# GateDrive_schem.net
KiCad netlist of a schematic drawn in Altium Designer
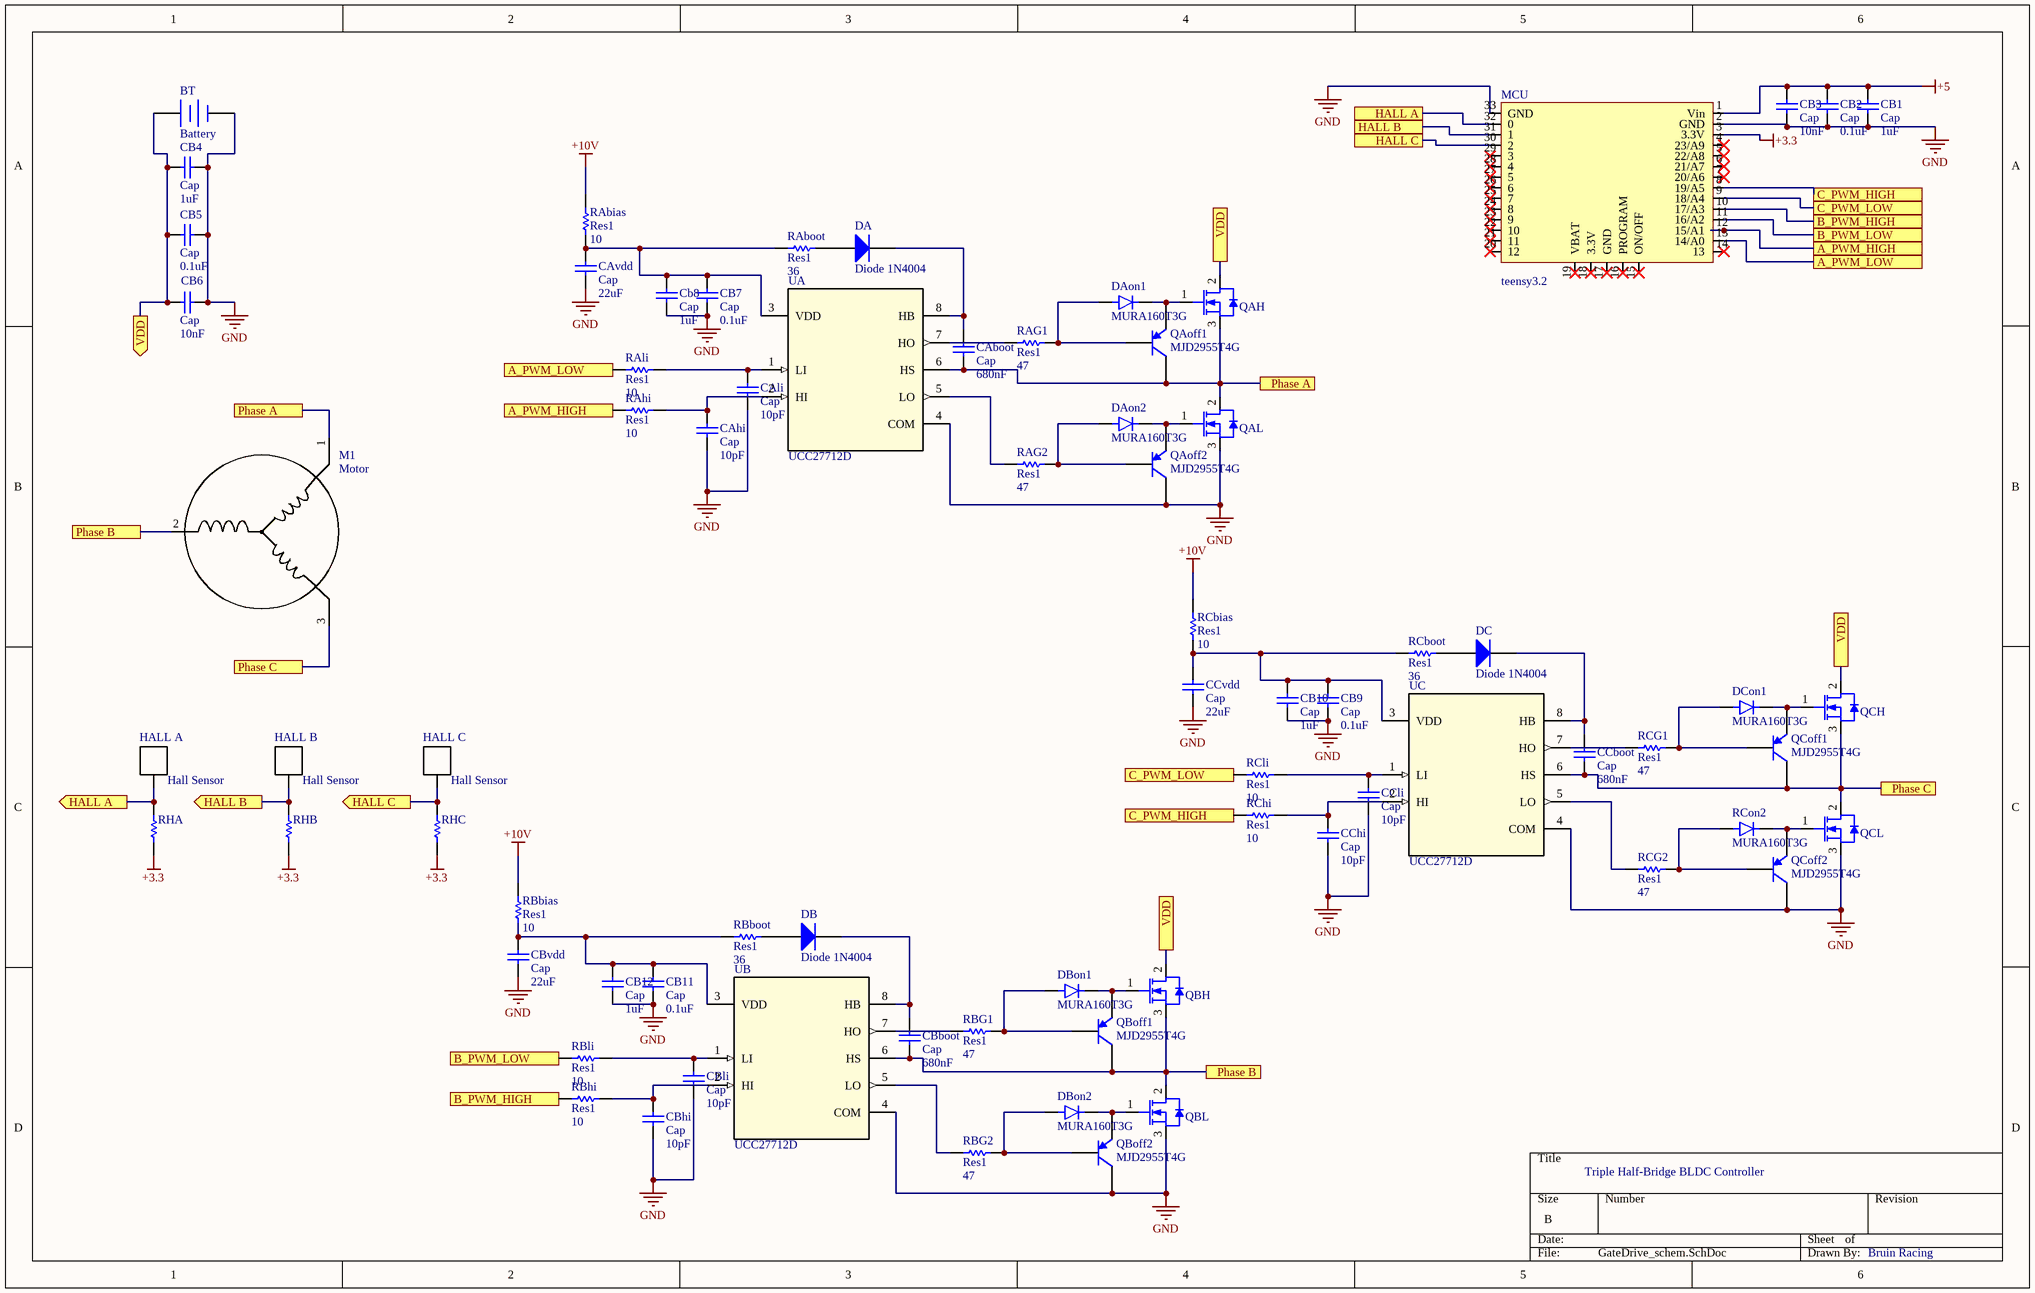
[diagram p0: GateDrive_schem.SchDoc]

(export (version "E")
  (design (tool "Eeschema 10.0.6"))
  (components
    (comp (ref "BT")
      (value "Battery")
      (footprint "BAT-2")
      (description "Multicell Battery")
      (fields (field (name "PUBLISHER") "Altium Limited"))
      (libsource (lib "Miscellaneous Devices") (part "Battery"))
    )
    (comp (ref "CAboot")
      (value "Cap")
      (footprint "RAD-0.3")
      (description "Capacitor")
      (fields (field (name "ALTIUM_VALUE") "680nF") (field (name "PUBLISHER") "Altium Limited"))
      (libsource (lib "Miscellaneous Devices") (part "Cap"))
    )
    (comp (ref "CAhi")
      (value "Cap")
      (footprint "RAD-0.3")
      (description "Capacitor")
      (fields (field (name "ALTIUM_VALUE") "10pF") (field (name "PUBLISHER") "Altium Limited"))
      (libsource (lib "Miscellaneous Devices") (part "Cap"))
    )
    (comp (ref "CAli")
      (value "Cap")
      (footprint "RAD-0.3")
      (description "Capacitor")
      (fields (field (name "ALTIUM_VALUE") "10pF") (field (name "PUBLISHER") "Altium Limited"))
      (libsource (lib "Miscellaneous Devices") (part "Cap"))
    )
    (comp (ref "CAvdd")
      (value "Cap")
      (footprint "RAD-0.3")
      (description "Capacitor")
      (fields (field (name "ALTIUM_VALUE") "22uF") (field (name "PUBLISHER") "Altium Limited"))
      (libsource (lib "Miscellaneous Devices") (part "Cap"))
    )
    (comp (ref "CB1")
      (value "Cap")
      (footprint "RAD-0.3")
      (description "Capacitor")
      (fields (field (name "ALTIUM_VALUE") "1uF") (field (name "PUBLISHER") "Altium Limited"))
      (libsource (lib "Miscellaneous Devices") (part "Cap"))
    )
    (comp (ref "CB2")
      (value "Cap")
      (footprint "RAD-0.3")
      (description "Capacitor")
      (fields (field (name "ALTIUM_VALUE") "0.1uF") (field (name "PUBLISHER") "Altium Limited"))
      (libsource (lib "Miscellaneous Devices") (part "Cap"))
    )
    (comp (ref "CB3")
      (value "Cap")
      (footprint "RAD-0.3")
      (description "Capacitor")
      (fields (field (name "ALTIUM_VALUE") "10nF") (field (name "PUBLISHER") "Altium Limited"))
      (libsource (lib "Miscellaneous Devices") (part "Cap"))
    )
    (comp (ref "CB4")
      (value "Cap")
      (footprint "RAD-0.3")
      (description "Capacitor")
      (fields (field (name "ALTIUM_VALUE") "1uF") (field (name "PUBLISHER") "Altium Limited"))
      (libsource (lib "Miscellaneous Devices") (part "Cap"))
    )
    (comp (ref "CB5")
      (value "Cap")
      (footprint "RAD-0.3")
      (description "Capacitor")
      (fields (field (name "ALTIUM_VALUE") "0.1uF") (field (name "PUBLISHER") "Altium Limited"))
      (libsource (lib "Miscellaneous Devices") (part "Cap"))
    )
    (comp (ref "CB6")
      (value "Cap")
      (footprint "RAD-0.3")
      (description "Capacitor")
      (fields (field (name "ALTIUM_VALUE") "10nF") (field (name "PUBLISHER") "Altium Limited"))
      (libsource (lib "Miscellaneous Devices") (part "Cap"))
    )
    (comp (ref "CB7")
      (value "Cap")
      (footprint "RAD-0.3")
      (description "Capacitor")
      (fields (field (name "ALTIUM_VALUE") "0.1uF") (field (name "PUBLISHER") "Altium Limited"))
      (libsource (lib "Miscellaneous Devices") (part "Cap"))
    )
    (comp (ref "Cb8")
      (value "Cap")
      (footprint "RAD-0.3")
      (description "Capacitor")
      (fields (field (name "ALTIUM_VALUE") "1uF") (field (name "PUBLISHER") "Altium Limited"))
      (libsource (lib "Miscellaneous Devices") (part "Cap"))
    )
    (comp (ref "CB9")
      (value "Cap")
      (footprint "RAD-0.3")
      (description "Capacitor")
      (fields (field (name "ALTIUM_VALUE") "0.1uF") (field (name "PUBLISHER") "Altium Limited"))
      (libsource (lib "Miscellaneous Devices") (part "Cap"))
    )
    (comp (ref "CB10")
      (value "Cap")
      (footprint "RAD-0.3")
      (description "Capacitor")
      (fields (field (name "ALTIUM_VALUE") "1uF") (field (name "PUBLISHER") "Altium Limited"))
      (libsource (lib "Miscellaneous Devices") (part "Cap"))
    )
    (comp (ref "CB11")
      (value "Cap")
      (footprint "RAD-0.3")
      (description "Capacitor")
      (fields (field (name "ALTIUM_VALUE") "0.1uF") (field (name "PUBLISHER") "Altium Limited"))
      (libsource (lib "Miscellaneous Devices") (part "Cap"))
    )
    (comp (ref "CB12")
      (value "Cap")
      (footprint "RAD-0.3")
      (description "Capacitor")
      (fields (field (name "ALTIUM_VALUE") "1uF") (field (name "PUBLISHER") "Altium Limited"))
      (libsource (lib "Miscellaneous Devices") (part "Cap"))
    )
    (comp (ref "CBboot")
      (value "Cap")
      (footprint "RAD-0.3")
      (description "Capacitor")
      (fields (field (name "ALTIUM_VALUE") "680nF") (field (name "PUBLISHER") "Altium Limited"))
      (libsource (lib "Miscellaneous Devices") (part "Cap"))
    )
    (comp (ref "CBhi")
      (value "Cap")
      (footprint "RAD-0.3")
      (description "Capacitor")
      (fields (field (name "ALTIUM_VALUE") "10pF") (field (name "PUBLISHER") "Altium Limited"))
      (libsource (lib "Miscellaneous Devices") (part "Cap"))
    )
    (comp (ref "CBli")
      (value "Cap")
      (footprint "RAD-0.3")
      (description "Capacitor")
      (fields (field (name "ALTIUM_VALUE") "10pF") (field (name "PUBLISHER") "Altium Limited"))
      (libsource (lib "Miscellaneous Devices") (part "Cap"))
    )
    (comp (ref "CBvdd")
      (value "Cap")
      (footprint "RAD-0.3")
      (description "Capacitor")
      (fields (field (name "ALTIUM_VALUE") "22uF") (field (name "PUBLISHER") "Altium Limited"))
      (libsource (lib "Miscellaneous Devices") (part "Cap"))
    )
    (comp (ref "CCboot")
      (value "Cap")
      (footprint "RAD-0.3")
      (description "Capacitor")
      (fields (field (name "ALTIUM_VALUE") "680nF") (field (name "PUBLISHER") "Altium Limited"))
      (libsource (lib "Miscellaneous Devices") (part "Cap"))
    )
    (comp (ref "CChi")
      (value "Cap")
      (footprint "RAD-0.3")
      (description "Capacitor")
      (fields (field (name "ALTIUM_VALUE") "10pF") (field (name "PUBLISHER") "Altium Limited"))
      (libsource (lib "Miscellaneous Devices") (part "Cap"))
    )
    (comp (ref "CCli")
      (value "Cap")
      (footprint "RAD-0.3")
      (description "Capacitor")
      (fields (field (name "ALTIUM_VALUE") "10pF") (field (name "PUBLISHER") "Altium Limited"))
      (libsource (lib "Miscellaneous Devices") (part "Cap"))
    )
    (comp (ref "CCvdd")
      (value "Cap")
      (footprint "RAD-0.3")
      (description "Capacitor")
      (fields (field (name "ALTIUM_VALUE") "22uF") (field (name "PUBLISHER") "Altium Limited"))
      (libsource (lib "Miscellaneous Devices") (part "Cap"))
    )
    (comp (ref "DA")
      (value "Diode 1N4004")
      (footprint "DO-41")
      (description "1 Amp General Purpose Rectifier")
      (fields (field (name "PUBLISHER") "Altium Limited"))
      (libsource (lib "Miscellaneous Devices") (part "Diode 1N4004"))
    )
    (comp (ref "DAon1")
      (value "MURA160T3G")
      (footprint "DIOM5226X220N")
      (description "Diode Standard 600V 1A Surface Mount SMA")
      (fields (field (name "MF") "ON Semiconductor"))
      (libsource (lib "MURA160T3G") (part "MURA160T3G"))
    )
    (comp (ref "DAon2")
      (value "MURA160T3G")
      (footprint "DIOM5226X220N")
      (description "Diode Standard 600V 1A Surface Mount SMA")
      (fields (field (name "MF") "ON Semiconductor"))
      (libsource (lib "MURA160T3G") (part "MURA160T3G"))
    )
    (comp (ref "DB")
      (value "Diode 1N4004")
      (footprint "DO-41")
      (description "1 Amp General Purpose Rectifier")
      (fields (field (name "PUBLISHER") "Altium Limited"))
      (libsource (lib "Miscellaneous Devices") (part "Diode 1N4004"))
    )
    (comp (ref "DBon1")
      (value "MURA160T3G")
      (footprint "DIOM5226X220N")
      (description "Diode Standard 600V 1A Surface Mount SMA")
      (fields (field (name "MF") "ON Semiconductor"))
      (libsource (lib "MURA160T3G") (part "MURA160T3G"))
    )
    (comp (ref "DBon2")
      (value "MURA160T3G")
      (footprint "DIOM5226X220N")
      (description "Diode Standard 600V 1A Surface Mount SMA")
      (fields (field (name "MF") "ON Semiconductor"))
      (libsource (lib "MURA160T3G") (part "MURA160T3G"))
    )
    (comp (ref "DC")
      (value "Diode 1N4004")
      (footprint "DO-41")
      (description "1 Amp General Purpose Rectifier")
      (fields (field (name "PUBLISHER") "Altium Limited"))
      (libsource (lib "Miscellaneous Devices") (part "Diode 1N4004"))
    )
    (comp (ref "DCon1")
      (value "MURA160T3G")
      (footprint "DIOM5226X220N")
      (description "Diode Standard 600V 1A Surface Mount SMA")
      (fields (field (name "MF") "ON Semiconductor"))
      (libsource (lib "MURA160T3G") (part "MURA160T3G"))
    )
    (comp (ref "HALL A")
      (value "Hall Sensor")
      (footprint "A single pin")
      (libsource (lib "Schlib1") (part "Hall Sensor"))
    )
    (comp (ref "HALL B")
      (value "Hall Sensor")
      (footprint "A single pin")
      (libsource (lib "Schlib1") (part "Hall Sensor"))
    )
    (comp (ref "HALL C")
      (value "Hall Sensor")
      (footprint "A single pin")
      (libsource (lib "Schlib1") (part "Hall Sensor"))
    )
    (comp (ref "M1") (value "Motor") (footprint "Motor") (libsource (lib "Schlib1") (part "Motor")))
    (comp (ref "MCU") (value "teensy3.2") (footprint "teensy3.2") (libsource (lib "BLDC") (part "teensy3.2")))
    (comp (ref "QAH") (value "INFINEON") (footprint "MOSFET-2") (libsource (lib "BLDC") (part "INFINEON")))
    (comp (ref "QAL") (value "INFINEON") (footprint "MOSFET-2") (libsource (lib "BLDC") (part "INFINEON")))
    (comp (ref "QAoff1")
      (value "MJD2955T4G")
      (footprint "MJD2955T4G")
      (description "PNP Bipolar Transistor")
      (fields (field (name "PUBLISHER") "Altium Limited"))
      (libsource (lib "Miscellaneous Devices") (part "PNP"))
    )
    (comp (ref "QAoff2")
      (value "MJD2955T4G")
      (footprint "MJD2955T4G")
      (description "PNP Bipolar Transistor")
      (fields (field (name "PUBLISHER") "Altium Limited"))
      (libsource (lib "Miscellaneous Devices") (part "PNP"))
    )
    (comp (ref "QBH") (value "INFINEON") (footprint "MOSFET-2") (libsource (lib "BLDC") (part "INFINEON")))
    (comp (ref "QBL") (value "INFINEON") (footprint "MOSFET-2") (libsource (lib "BLDC") (part "INFINEON")))
    (comp (ref "QBoff1")
      (value "MJD2955T4G")
      (footprint "MJD2955T4G")
      (description "PNP Bipolar Transistor")
      (fields (field (name "PUBLISHER") "Altium Limited"))
      (libsource (lib "Miscellaneous Devices") (part "PNP"))
    )
    (comp (ref "QBoff2")
      (value "MJD2955T4G")
      (footprint "MJD2955T4G")
      (description "PNP Bipolar Transistor")
      (fields (field (name "PUBLISHER") "Altium Limited"))
      (libsource (lib "Miscellaneous Devices") (part "PNP"))
    )
    (comp (ref "QCH") (value "INFINEON") (footprint "MOSFET-2") (libsource (lib "BLDC") (part "INFINEON")))
    (comp (ref "QCL") (value "INFINEON") (footprint "MOSFET-2") (libsource (lib "BLDC") (part "INFINEON")))
    (comp (ref "QCoff1")
      (value "MJD2955T4G")
      (footprint "MJD2955T4G")
      (description "PNP Bipolar Transistor")
      (fields (field (name "PUBLISHER") "Altium Limited"))
      (libsource (lib "Miscellaneous Devices") (part "PNP"))
    )
    (comp (ref "QCoff2")
      (value "MJD2955T4G")
      (footprint "MJD2955T4G")
      (description "PNP Bipolar Transistor")
      (fields (field (name "PUBLISHER") "Altium Limited"))
      (libsource (lib "Miscellaneous Devices") (part "PNP"))
    )
    (comp (ref "RAbias")
      (value "Res1")
      (footprint "RESC2013X50X30LL20T20")
      (description "Resistor")
      (fields (field (name "ALTIUM_VALUE") "10") (field (name "PUBLISHER") "Altium Limited"))
      (libsource (lib "Miscellaneous Devices") (part "Res1"))
    )
    (comp (ref "RAboot")
      (value "Res1")
      (footprint "RESC2013X50X30LL20T20")
      (description "Resistor")
      (fields (field (name "ALTIUM_VALUE") "36") (field (name "PUBLISHER") "Altium Limited"))
      (libsource (lib "Miscellaneous Devices") (part "Res1"))
    )
    (comp (ref "RAG1")
      (value "Res1")
      (footprint "RESC2013X50X30LL20T20")
      (description "Resistor")
      (fields (field (name "ALTIUM_VALUE") "47") (field (name "PUBLISHER") "Altium Limited"))
      (libsource (lib "Miscellaneous Devices") (part "Res1"))
    )
    (comp (ref "RAG2")
      (value "Res1")
      (footprint "RESC2013X50X30LL20T20")
      (description "Resistor")
      (fields (field (name "ALTIUM_VALUE") "47") (field (name "PUBLISHER") "Altium Limited"))
      (libsource (lib "Miscellaneous Devices") (part "Res1"))
    )
    (comp (ref "RAhi")
      (value "Res1")
      (footprint "RESC2013X50X30LL20T20")
      (description "Resistor")
      (fields (field (name "ALTIUM_VALUE") "10") (field (name "PUBLISHER") "Altium Limited"))
      (libsource (lib "Miscellaneous Devices") (part "Res1"))
    )
    (comp (ref "RAli")
      (value "Res1")
      (footprint "RESC2013X50X30LL20T20")
      (description "Resistor")
      (fields (field (name "ALTIUM_VALUE") "10") (field (name "PUBLISHER") "Altium Limited"))
      (libsource (lib "Miscellaneous Devices") (part "Res1"))
    )
    (comp (ref "RBbias")
      (value "Res1")
      (footprint "RESC2013X50X30LL20T20")
      (description "Resistor")
      (fields (field (name "ALTIUM_VALUE") "10") (field (name "PUBLISHER") "Altium Limited"))
      (libsource (lib "Miscellaneous Devices") (part "Res1"))
    )
    (comp (ref "RBboot")
      (value "Res1")
      (footprint "RESC2013X50X30LL20T20")
      (description "Resistor")
      (fields (field (name "ALTIUM_VALUE") "36") (field (name "PUBLISHER") "Altium Limited"))
      (libsource (lib "Miscellaneous Devices") (part "Res1"))
    )
    (comp (ref "RBG1")
      (value "Res1")
      (footprint "RESC2013X50X30LL20T20")
      (description "Resistor")
      (fields (field (name "ALTIUM_VALUE") "47") (field (name "PUBLISHER") "Altium Limited"))
      (libsource (lib "Miscellaneous Devices") (part "Res1"))
    )
    (comp (ref "RBG2")
      (value "Res1")
      (footprint "RESC2013X50X30LL20T20")
      (description "Resistor")
      (fields (field (name "ALTIUM_VALUE") "47") (field (name "PUBLISHER") "Altium Limited"))
      (libsource (lib "Miscellaneous Devices") (part "Res1"))
    )
    (comp (ref "RBhi")
      (value "Res1")
      (footprint "RESC2013X50X30LL20T20")
      (description "Resistor")
      (fields (field (name "ALTIUM_VALUE") "10") (field (name "PUBLISHER") "Altium Limited"))
      (libsource (lib "Miscellaneous Devices") (part "Res1"))
    )
    (comp (ref "RBli")
      (value "Res1")
      (footprint "RESC2013X50X30LL20T20")
      (description "Resistor")
      (fields (field (name "ALTIUM_VALUE") "10") (field (name "PUBLISHER") "Altium Limited"))
      (libsource (lib "Miscellaneous Devices") (part "Res1"))
    )
    (comp (ref "RCbias")
      (value "Res1")
      (footprint "RESC2013X50X30LL20T20")
      (description "Resistor")
      (fields (field (name "ALTIUM_VALUE") "10") (field (name "PUBLISHER") "Altium Limited"))
      (libsource (lib "Miscellaneous Devices") (part "Res1"))
    )
    (comp (ref "RCboot")
      (value "Res1")
      (footprint "RESC2013X50X30LL20T20")
      (description "Resistor")
      (fields (field (name "ALTIUM_VALUE") "36") (field (name "PUBLISHER") "Altium Limited"))
      (libsource (lib "Miscellaneous Devices") (part "Res1"))
    )
    (comp (ref "RCG1")
      (value "Res1")
      (footprint "RESC2013X50X30LL20T20")
      (description "Resistor")
      (fields (field (name "ALTIUM_VALUE") "47") (field (name "PUBLISHER") "Altium Limited"))
      (libsource (lib "Miscellaneous Devices") (part "Res1"))
    )
    (comp (ref "RCG2")
      (value "Res1")
      (footprint "RESC2013X50X30LL20T20")
      (description "Resistor")
      (fields (field (name "ALTIUM_VALUE") "47") (field (name "PUBLISHER") "Altium Limited"))
      (libsource (lib "Miscellaneous Devices") (part "Res1"))
    )
    (comp (ref "RChi")
      (value "Res1")
      (footprint "RESC2013X50X30LL20T20")
      (description "Resistor")
      (fields (field (name "ALTIUM_VALUE") "10") (field (name "PUBLISHER") "Altium Limited"))
      (libsource (lib "Miscellaneous Devices") (part "Res1"))
    )
    (comp (ref "RCli")
      (value "Res1")
      (footprint "RESC2013X50X30LL20T20")
      (description "Resistor")
      (fields (field (name "ALTIUM_VALUE") "10") (field (name "PUBLISHER") "Altium Limited"))
      (libsource (lib "Miscellaneous Devices") (part "Res1"))
    )
    (comp (ref "RCon2")
      (value "MURA160T3G")
      (footprint "DIOM5226X220N")
      (description "Diode Standard 600V 1A Surface Mount SMA")
      (fields (field (name "MF") "ON Semiconductor"))
      (libsource (lib "MURA160T3G") (part "MURA160T3G"))
    )
    (comp (ref "RHA")
      (value "CRCW08050000Z0EA")
      (footprint "RESC2013X50X30LL20T20")
      (fields (field (name "MANUFACTURER") "Vishay Dale"))
      (libsource (lib "Altium Content Vault") (part "RES"))
    )
    (comp (ref "RHB")
      (value "CRCW08050000Z0EA")
      (footprint "RESC2013X50X30LL20T20")
      (fields (field (name "MANUFACTURER") "Vishay Dale"))
      (libsource (lib "Altium Content Vault") (part "RES"))
    )
    (comp (ref "RHC")
      (value "CRCW08050000Z0EA")
      (footprint "RESC2013X50X30LL20T20")
      (fields (field (name "MANUFACTURER") "Vishay Dale"))
      (libsource (lib "Altium Content Vault") (part "RES"))
    )
    (comp (ref "UA")
      (value "UCC27712D")
      (footprint "D0008A_N")
      (description "No Description Available")
      (fields
        (field (name "PARTNUMBER") "UCC27712DR")
        (field (name "MANUFACTURER") "Texas Instruments")
        (field (name "COPYRIGHT") "Copyright (C) 2018 Accelerated Designs. All rights reserved")
      )
      (libsource (lib "UCC277") (part "UCC27712D"))
    )
    (comp (ref "UB")
      (value "UCC27712D")
      (footprint "D0008A_N")
      (description "No Description Available")
      (fields
        (field (name "PARTNUMBER") "UCC27712DR")
        (field (name "MANUFACTURER") "Texas Instruments")
        (field (name "COPYRIGHT") "Copyright (C) 2018 Accelerated Designs. All rights reserved")
      )
      (libsource (lib "UCC277") (part "UCC27712D"))
    )
    (comp (ref "UC")
      (value "UCC27712D")
      (footprint "D0008A_N")
      (description "No Description Available")
      (fields
        (field (name "PARTNUMBER") "UCC27712DR")
        (field (name "MANUFACTURER") "Texas Instruments")
        (field (name "COPYRIGHT") "Copyright (C) 2018 Accelerated Designs. All rights reserved")
      )
      (libsource (lib "UCC277") (part "UCC27712D"))
    )
  )
  (nets
    (net (code "1") (name "+3.3") (class "Default")
      (node (ref "MCU") (pin "3") (pinfunction "3.3V_3") (pintype "passive"))
      (node (ref "RHA") (pin "1") (pinfunction "1_1") (pintype "passive"))
      (node (ref "RHB") (pin "1") (pinfunction "1_1") (pintype "passive"))
      (node (ref "RHC") (pin "1") (pinfunction "1_1") (pintype "passive"))
    )
    (net (code "2") (name "+5") (class "Default")
      (node (ref "CB1") (pin "2") (pinfunction "2_2") (pintype "passive"))
      (node (ref "CB2") (pin "2") (pinfunction "2_2") (pintype "passive"))
      (node (ref "CB3") (pin "2") (pinfunction "2_2") (pintype "passive"))
      (node (ref "MCU") (pin "1") (pinfunction "Vin_1") (pintype "passive"))
    )
    (net (code "3") (name "+10V") (class "Default")
      (node (ref "RAbias") (pin "2") (pinfunction "2_2") (pintype "passive"))
      (node (ref "RBbias") (pin "2") (pinfunction "2_2") (pintype "passive"))
      (node (ref "RCbias") (pin "2") (pinfunction "2_2") (pintype "passive"))
    )
    (net (code "4") (name "/A_PWM_HIGH") (class "Default")
      (node (ref "MCU") (pin "12") (pinfunction "15/A1_12") (pintype "passive"))
      (node (ref "RAhi") (pin "1") (pinfunction "1_1") (pintype "passive"))
    )
    (net (code "5") (name "/A_PWM_LOW") (class "Default")
      (node (ref "MCU") (pin "13") (pinfunction "14/A0_13") (pintype "passive"))
      (node (ref "RAli") (pin "1") (pinfunction "1_1") (pintype "passive"))
    )
    (net (code "6") (name "/B_PWM_HIGH") (class "Default")
      (node (ref "MCU") (pin "10") (pinfunction "17/A3_10") (pintype "passive"))
      (node (ref "RBhi") (pin "1") (pinfunction "1_1") (pintype "passive"))
    )
    (net (code "7") (name "/B_PWM_LOW") (class "Default")
      (node (ref "MCU") (pin "11") (pinfunction "16/A2_11") (pintype "passive"))
      (node (ref "RBli") (pin "1") (pinfunction "1_1") (pintype "passive"))
    )
    (net (code "8") (name "/C_PWM_HIGH") (class "Default")
      (node (ref "MCU") (pin "8") (pinfunction "19/A5_8") (pintype "passive"))
      (node (ref "RChi") (pin "1") (pinfunction "1_1") (pintype "passive"))
    )
    (net (code "9") (name "/C_PWM_LOW") (class "Default")
      (node (ref "MCU") (pin "9") (pinfunction "18/A4_9") (pintype "passive"))
      (node (ref "RCli") (pin "1") (pinfunction "1_1") (pintype "passive"))
    )
    (net (code "10") (name "/HALL A") (class "Default")
      (node (ref "HALL A") (pin "0") (pintype "passive"))
      (node (ref "MCU") (pin "32") (pinfunction "0_32") (pintype "passive"))
      (node (ref "RHA") (pin "2") (pinfunction "2_2") (pintype "passive"))
    )
    (net (code "11") (name "/HALL B") (class "Default")
      (node (ref "HALL B") (pin "0") (pintype "passive"))
      (node (ref "MCU") (pin "31") (pinfunction "1_31") (pintype "passive"))
      (node (ref "RHB") (pin "2") (pinfunction "2_2") (pintype "passive"))
    )
    (net (code "12") (name "/HALL C") (class "Default")
      (node (ref "HALL C") (pin "0") (pintype "passive"))
      (node (ref "MCU") (pin "30") (pinfunction "2_30") (pintype "passive"))
      (node (ref "RHC") (pin "2") (pinfunction "2_2") (pintype "passive"))
    )
    (net (code "13") (name "/Phase A") (class "Default")
      (node (ref "CAboot") (pin "1") (pinfunction "1_1") (pintype "passive"))
      (node (ref "M1") (pin "1") (pinfunction "A_1") (pintype "passive"))
      (node (ref "QAH") (pin "3") (pinfunction "S_3") (pintype "passive"))
      (node (ref "QAL") (pin "2") (pinfunction "D_2") (pintype "passive"))
      (node (ref "QAoff1") (pin "1") (pinfunction "C_1") (pintype "passive"))
      (node (ref "UA") (pin "6") (pinfunction "HS_6") (pintype "passive"))
    )
    (net (code "14") (name "/Phase B") (class "Default")
      (node (ref "CBboot") (pin "1") (pinfunction "1_1") (pintype "passive"))
      (node (ref "M1") (pin "2") (pinfunction "B_2") (pintype "passive"))
      (node (ref "QBH") (pin "3") (pinfunction "S_3") (pintype "passive"))
      (node (ref "QBL") (pin "2") (pinfunction "D_2") (pintype "passive"))
      (node (ref "QBoff1") (pin "1") (pinfunction "C_1") (pintype "passive"))
      (node (ref "UB") (pin "6") (pinfunction "HS_6") (pintype "passive"))
    )
    (net (code "15") (name "/Phase C") (class "Default")
      (node (ref "CCboot") (pin "1") (pinfunction "1_1") (pintype "passive"))
      (node (ref "M1") (pin "3") (pinfunction "C_3") (pintype "passive"))
      (node (ref "QCH") (pin "3") (pinfunction "S_3") (pintype "passive"))
      (node (ref "QCL") (pin "2") (pinfunction "D_2") (pintype "passive"))
      (node (ref "QCoff1") (pin "1") (pinfunction "C_1") (pintype "passive"))
      (node (ref "UC") (pin "6") (pinfunction "HS_6") (pintype "passive"))
    )
    (net (code "16") (name "/VDD") (class "Default")
      (node (ref "BT") (pin "1") (pinfunction "+_1") (pintype "passive"))
      (node (ref "CB4") (pin "1") (pinfunction "1_1") (pintype "passive"))
      (node (ref "CB5") (pin "2") (pinfunction "2_2") (pintype "passive"))
      (node (ref "CB6") (pin "2") (pinfunction "2_2") (pintype "passive"))
      (node (ref "QAH") (pin "2") (pinfunction "D_2") (pintype "passive"))
      (node (ref "QBH") (pin "2") (pinfunction "D_2") (pintype "passive"))
      (node (ref "QCH") (pin "2") (pinfunction "D_2") (pintype "passive"))
    )
    (net (code "17") (name "GND") (class "Default")
      (node (ref "BT") (pin "2") (pinfunction "-_2") (pintype "passive"))
      (node (ref "CAhi") (pin "1") (pinfunction "1_1") (pintype "passive"))
      (node (ref "CAli") (pin "1") (pinfunction "1_1") (pintype "passive"))
      (node (ref "CAvdd") (pin "1") (pinfunction "1_1") (pintype "passive"))
      (node (ref "CB1") (pin "1") (pinfunction "1_1") (pintype "passive"))
      (node (ref "CB10") (pin "1") (pinfunction "1_1") (pintype "passive"))
      (node (ref "CB11") (pin "1") (pinfunction "1_1") (pintype "passive"))
      (node (ref "CB12") (pin "1") (pinfunction "1_1") (pintype "passive"))
      (node (ref "CB2") (pin "1") (pinfunction "1_1") (pintype "passive"))
      (node (ref "CB3") (pin "1") (pinfunction "1_1") (pintype "passive"))
      (node (ref "CB4") (pin "2") (pinfunction "2_2") (pintype "passive"))
      (node (ref "CB5") (pin "1") (pinfunction "1_1") (pintype "passive"))
      (node (ref "CB6") (pin "1") (pinfunction "1_1") (pintype "passive"))
      (node (ref "CB7") (pin "1") (pinfunction "1_1") (pintype "passive"))
      (node (ref "CB9") (pin "1") (pinfunction "1_1") (pintype "passive"))
      (node (ref "CBhi") (pin "1") (pinfunction "1_1") (pintype "passive"))
      (node (ref "CBli") (pin "1") (pinfunction "1_1") (pintype "passive"))
      (node (ref "CBvdd") (pin "1") (pinfunction "1_1") (pintype "passive"))
      (node (ref "CChi") (pin "1") (pinfunction "1_1") (pintype "passive"))
      (node (ref "CCli") (pin "1") (pinfunction "1_1") (pintype "passive"))
      (node (ref "CCvdd") (pin "1") (pinfunction "1_1") (pintype "passive"))
      (node (ref "Cb8") (pin "1") (pinfunction "1_1") (pintype "passive"))
      (node (ref "MCU") (pin "2") (pinfunction "GND_2") (pintype "passive"))
      (node (ref "MCU") (pin "33") (pinfunction "GND_33") (pintype "passive"))
      (node (ref "QAL") (pin "3") (pinfunction "S_3") (pintype "passive"))
      (node (ref "QAoff2") (pin "1") (pinfunction "C_1") (pintype "passive"))
      (node (ref "QBL") (pin "3") (pinfunction "S_3") (pintype "passive"))
      (node (ref "QBoff2") (pin "1") (pinfunction "C_1") (pintype "passive"))
      (node (ref "QCL") (pin "3") (pinfunction "S_3") (pintype "passive"))
      (node (ref "QCoff2") (pin "1") (pinfunction "C_1") (pintype "passive"))
      (node (ref "UA") (pin "4") (pinfunction "COM_4") (pintype "power_in"))
      (node (ref "UB") (pin "4") (pinfunction "COM_4") (pintype "power_in"))
      (node (ref "UC") (pin "4") (pinfunction "COM_4") (pintype "power_in"))
    )
    (net (code "18") (name "Net-(DA-A)") (class "Default")
      (node (ref "DA") (pin "1") (pinfunction "A_1") (pintype "passive"))
      (node (ref "RAboot") (pin "1") (pinfunction "1_1") (pintype "passive"))
    )
    (net (code "19") (name "Net-(DA-K)") (class "Default")
      (node (ref "CAboot") (pin "2") (pinfunction "2_2") (pintype "passive"))
      (node (ref "DA") (pin "2") (pinfunction "K_2") (pintype "passive"))
      (node (ref "UA") (pin "8") (pinfunction "HB_8") (pintype "power_in"))
    )
    (net (code "20") (name "Net-(DAon1-K)") (class "Default")
      (node (ref "DAon1") (pin "C") (pinfunction "K_C") (pintype "passive"))
      (node (ref "QAH") (pin "1") (pinfunction "G_1") (pintype "passive"))
      (node (ref "QAoff1") (pin "3") (pinfunction "E_3") (pintype "passive"))
    )
    (net (code "21") (name "Net-(DAon2-K)") (class "Default")
      (node (ref "DAon2") (pin "C") (pinfunction "K_C") (pintype "passive"))
      (node (ref "QAL") (pin "1") (pinfunction "G_1") (pintype "passive"))
      (node (ref "QAoff2") (pin "3") (pinfunction "E_3") (pintype "passive"))
    )
    (net (code "22") (name "Net-(DB-A)") (class "Default")
      (node (ref "DB") (pin "1") (pinfunction "A_1") (pintype "passive"))
      (node (ref "RBboot") (pin "1") (pinfunction "1_1") (pintype "passive"))
    )
    (net (code "23") (name "Net-(DB-K)") (class "Default")
      (node (ref "CBboot") (pin "2") (pinfunction "2_2") (pintype "passive"))
      (node (ref "DB") (pin "2") (pinfunction "K_2") (pintype "passive"))
      (node (ref "UB") (pin "8") (pinfunction "HB_8") (pintype "power_in"))
    )
    (net (code "24") (name "Net-(DBon1-K)") (class "Default")
      (node (ref "DBon1") (pin "C") (pinfunction "K_C") (pintype "passive"))
      (node (ref "QBH") (pin "1") (pinfunction "G_1") (pintype "passive"))
      (node (ref "QBoff1") (pin "3") (pinfunction "E_3") (pintype "passive"))
    )
    (net (code "25") (name "Net-(DBon2-K)") (class "Default")
      (node (ref "DBon2") (pin "C") (pinfunction "K_C") (pintype "passive"))
      (node (ref "QBL") (pin "1") (pinfunction "G_1") (pintype "passive"))
      (node (ref "QBoff2") (pin "3") (pinfunction "E_3") (pintype "passive"))
    )
    (net (code "26") (name "Net-(DC-A)") (class "Default")
      (node (ref "DC") (pin "1") (pinfunction "A_1") (pintype "passive"))
      (node (ref "RCboot") (pin "1") (pinfunction "1_1") (pintype "passive"))
    )
    (net (code "27") (name "Net-(DC-K)") (class "Default")
      (node (ref "CCboot") (pin "2") (pinfunction "2_2") (pintype "passive"))
      (node (ref "DC") (pin "2") (pinfunction "K_2") (pintype "passive"))
      (node (ref "UC") (pin "8") (pinfunction "HB_8") (pintype "power_in"))
    )
    (net (code "28") (name "Net-(DCon1-K)") (class "Default")
      (node (ref "DCon1") (pin "C") (pinfunction "K_C") (pintype "passive"))
      (node (ref "QCH") (pin "1") (pinfunction "G_1") (pintype "passive"))
      (node (ref "QCoff1") (pin "3") (pinfunction "E_3") (pintype "passive"))
    )
    (net (code "29") (name "Net-(QAoff1-B)") (class "Default")
      (node (ref "DAon1") (pin "A") (pinfunction "A_A") (pintype "passive"))
      (node (ref "QAoff1") (pin "2") (pinfunction "B_2") (pintype "passive"))
      (node (ref "RAG1") (pin "2") (pinfunction "2_2") (pintype "passive"))
    )
    (net (code "30") (name "Net-(QAoff2-B)") (class "Default")
      (node (ref "DAon2") (pin "A") (pinfunction "A_A") (pintype "passive"))
      (node (ref "QAoff2") (pin "2") (pinfunction "B_2") (pintype "passive"))
      (node (ref "RAG2") (pin "2") (pinfunction "2_2") (pintype "passive"))
    )
    (net (code "31") (name "Net-(QBoff1-B)") (class "Default")
      (node (ref "DBon1") (pin "A") (pinfunction "A_A") (pintype "passive"))
      (node (ref "QBoff1") (pin "2") (pinfunction "B_2") (pintype "passive"))
      (node (ref "RBG1") (pin "2") (pinfunction "2_2") (pintype "passive"))
    )
    (net (code "32") (name "Net-(QBoff2-B)") (class "Default")
      (node (ref "DBon2") (pin "A") (pinfunction "A_A") (pintype "passive"))
      (node (ref "QBoff2") (pin "2") (pinfunction "B_2") (pintype "passive"))
      (node (ref "RBG2") (pin "2") (pinfunction "2_2") (pintype "passive"))
    )
    (net (code "33") (name "Net-(QCL-G)") (class "Default")
      (node (ref "QCL") (pin "1") (pinfunction "G_1") (pintype "passive"))
      (node (ref "QCoff2") (pin "3") (pinfunction "E_3") (pintype "passive"))
      (node (ref "RCon2") (pin "C") (pinfunction "K_C") (pintype "passive"))
    )
    (net (code "34") (name "Net-(QCoff1-B)") (class "Default")
      (node (ref "DCon1") (pin "A") (pinfunction "A_A") (pintype "passive"))
      (node (ref "QCoff1") (pin "2") (pinfunction "B_2") (pintype "passive"))
      (node (ref "RCG1") (pin "2") (pinfunction "2_2") (pintype "passive"))
    )
    (net (code "35") (name "Net-(QCoff2-B)") (class "Default")
      (node (ref "QCoff2") (pin "2") (pinfunction "B_2") (pintype "passive"))
      (node (ref "RCG2") (pin "2") (pinfunction "2_2") (pintype "passive"))
      (node (ref "RCon2") (pin "A") (pinfunction "A_A") (pintype "passive"))
    )
    (net (code "36") (name "Net-(UA-HI)") (class "Default")
      (node (ref "CAhi") (pin "2") (pinfunction "2_2") (pintype "passive"))
      (node (ref "RAhi") (pin "2") (pinfunction "2_2") (pintype "passive"))
      (node (ref "UA") (pin "2") (pinfunction "HI_2") (pintype "input"))
    )
    (net (code "37") (name "Net-(UA-HO)") (class "Default")
      (node (ref "RAG1") (pin "1") (pinfunction "1_1") (pintype "passive"))
      (node (ref "UA") (pin "7") (pinfunction "HO_7") (pintype "output"))
    )
    (net (code "38") (name "Net-(UA-LI)") (class "Default")
      (node (ref "CAli") (pin "2") (pinfunction "2_2") (pintype "passive"))
      (node (ref "RAli") (pin "2") (pinfunction "2_2") (pintype "passive"))
      (node (ref "UA") (pin "1") (pinfunction "LI_1") (pintype "input"))
    )
    (net (code "39") (name "Net-(UA-LO)") (class "Default")
      (node (ref "RAG2") (pin "1") (pinfunction "1_1") (pintype "passive"))
      (node (ref "UA") (pin "5") (pinfunction "LO_5") (pintype "output"))
    )
    (net (code "40") (name "Net-(UA-VDD)") (class "Default")
      (node (ref "CAvdd") (pin "2") (pinfunction "2_2") (pintype "passive"))
      (node (ref "CB7") (pin "2") (pinfunction "2_2") (pintype "passive"))
      (node (ref "Cb8") (pin "2") (pinfunction "2_2") (pintype "passive"))
      (node (ref "RAbias") (pin "1") (pinfunction "1_1") (pintype "passive"))
      (node (ref "RAboot") (pin "2") (pinfunction "2_2") (pintype "passive"))
      (node (ref "UA") (pin "3") (pinfunction "VDD_3") (pintype "power_in"))
    )
    (net (code "41") (name "Net-(UB-HI)") (class "Default")
      (node (ref "CBhi") (pin "2") (pinfunction "2_2") (pintype "passive"))
      (node (ref "RBhi") (pin "2") (pinfunction "2_2") (pintype "passive"))
      (node (ref "UB") (pin "2") (pinfunction "HI_2") (pintype "input"))
    )
    (net (code "42") (name "Net-(UB-HO)") (class "Default")
      (node (ref "RBG1") (pin "1") (pinfunction "1_1") (pintype "passive"))
      (node (ref "UB") (pin "7") (pinfunction "HO_7") (pintype "output"))
    )
    (net (code "43") (name "Net-(UB-LI)") (class "Default")
      (node (ref "CBli") (pin "2") (pinfunction "2_2") (pintype "passive"))
      (node (ref "RBli") (pin "2") (pinfunction "2_2") (pintype "passive"))
      (node (ref "UB") (pin "1") (pinfunction "LI_1") (pintype "input"))
    )
    (net (code "44") (name "Net-(UB-LO)") (class "Default")
      (node (ref "RBG2") (pin "1") (pinfunction "1_1") (pintype "passive"))
      (node (ref "UB") (pin "5") (pinfunction "LO_5") (pintype "output"))
    )
    (net (code "45") (name "Net-(UB-VDD)") (class "Default")
      (node (ref "CB11") (pin "2") (pinfunction "2_2") (pintype "passive"))
      (node (ref "CB12") (pin "2") (pinfunction "2_2") (pintype "passive"))
      (node (ref "CBvdd") (pin "2") (pinfunction "2_2") (pintype "passive"))
      (node (ref "RBbias") (pin "1") (pinfunction "1_1") (pintype "passive"))
      (node (ref "RBboot") (pin "2") (pinfunction "2_2") (pintype "passive"))
      (node (ref "UB") (pin "3") (pinfunction "VDD_3") (pintype "power_in"))
    )
    (net (code "46") (name "Net-(UC-HI)") (class "Default")
      (node (ref "CChi") (pin "2") (pinfunction "2_2") (pintype "passive"))
      (node (ref "RChi") (pin "2") (pinfunction "2_2") (pintype "passive"))
      (node (ref "UC") (pin "2") (pinfunction "HI_2") (pintype "input"))
    )
    (net (code "47") (name "Net-(UC-HO)") (class "Default")
      (node (ref "RCG1") (pin "1") (pinfunction "1_1") (pintype "passive"))
      (node (ref "UC") (pin "7") (pinfunction "HO_7") (pintype "output"))
    )
    (net (code "48") (name "Net-(UC-LI)") (class "Default")
      (node (ref "CCli") (pin "2") (pinfunction "2_2") (pintype "passive"))
      (node (ref "RCli") (pin "2") (pinfunction "2_2") (pintype "passive"))
      (node (ref "UC") (pin "1") (pinfunction "LI_1") (pintype "input"))
    )
    (net (code "49") (name "Net-(UC-LO)") (class "Default")
      (node (ref "RCG2") (pin "1") (pinfunction "1_1") (pintype "passive"))
      (node (ref "UC") (pin "5") (pinfunction "LO_5") (pintype "output"))
    )
    (net (code "50") (name "Net-(UC-VDD)") (class "Default")
      (node (ref "CB10") (pin "2") (pinfunction "2_2") (pintype "passive"))
      (node (ref "CB9") (pin "2") (pinfunction "2_2") (pintype "passive"))
      (node (ref "CCvdd") (pin "2") (pinfunction "2_2") (pintype "passive"))
      (node (ref "RCbias") (pin "1") (pinfunction "1_1") (pintype "passive"))
      (node (ref "RCboot") (pin "2") (pinfunction "2_2") (pintype "passive"))
      (node (ref "UC") (pin "3") (pinfunction "VDD_3") (pintype "power_in"))
    )
    (net (code "51") (name "unconnected-(MCU-3-Pad29)") (class "Default")
      (node (ref "MCU") (pin "29") (pinfunction "3_29") (pintype "passive+no_connect"))
    )
    (net (code "52") (name "unconnected-(MCU-3.3V-Pad18)") (class "Default")
      (node (ref "MCU") (pin "18") (pinfunction "3.3V_18") (pintype "passive+no_connect"))
    )
    (net (code "53") (name "unconnected-(MCU-4-Pad28)") (class "Default")
      (node (ref "MCU") (pin "28") (pinfunction "4_28") (pintype "passive+no_connect"))
    )
    (net (code "54") (name "unconnected-(MCU-5-Pad27)") (class "Default")
      (node (ref "MCU") (pin "27") (pinfunction "5_27") (pintype "passive+no_connect"))
    )
    (net (code "55") (name "unconnected-(MCU-6-Pad26)") (class "Default")
      (node (ref "MCU") (pin "26") (pinfunction "6_26") (pintype "passive+no_connect"))
    )
    (net (code "56") (name "unconnected-(MCU-7-Pad25)") (class "Default")
      (node (ref "MCU") (pin "25") (pinfunction "7_25") (pintype "passive+no_connect"))
    )
    (net (code "57") (name "unconnected-(MCU-8-Pad24)") (class "Default")
      (node (ref "MCU") (pin "24") (pinfunction "8_24") (pintype "passive+no_connect"))
    )
    (net (code "58") (name "unconnected-(MCU-9-Pad23)") (class "Default")
      (node (ref "MCU") (pin "23") (pinfunction "9_23") (pintype "passive+no_connect"))
    )
    (net (code "59") (name "unconnected-(MCU-10-Pad22)") (class "Default")
      (node (ref "MCU") (pin "22") (pinfunction "10_22") (pintype "passive+no_connect"))
    )
    (net (code "60") (name "unconnected-(MCU-11-Pad21)") (class "Default")
      (node (ref "MCU") (pin "21") (pinfunction "11_21") (pintype "passive+no_connect"))
    )
    (net (code "61") (name "unconnected-(MCU-12-Pad20)") (class "Default")
      (node (ref "MCU") (pin "20") (pinfunction "12_20") (pintype "passive+no_connect"))
    )
    (net (code "62") (name "unconnected-(MCU-13-Pad14)") (class "Default")
      (node (ref "MCU") (pin "14") (pinfunction "13_14") (pintype "passive+no_connect"))
    )
    (net (code "63") (name "unconnected-(MCU-20{slash}A6-Pad7)") (class "Default")
      (node (ref "MCU") (pin "7") (pinfunction "20/A6_7") (pintype "passive+no_connect"))
    )
    (net (code "64") (name "unconnected-(MCU-21{slash}A7-Pad6)") (class "Default")
      (node (ref "MCU") (pin "6") (pinfunction "21/A7_6") (pintype "passive+no_connect"))
    )
    (net (code "65") (name "unconnected-(MCU-22{slash}A8-Pad5)") (class "Default")
      (node (ref "MCU") (pin "5") (pinfunction "22/A8_5") (pintype "passive+no_connect"))
    )
    (net (code "66") (name "unconnected-(MCU-23{slash}A9-Pad4)") (class "Default")
      (node (ref "MCU") (pin "4") (pinfunction "23/A9_4") (pintype "passive+no_connect"))
    )
    (net (code "67") (name "unconnected-(MCU-GND-Pad17)") (class "Default")
      (node (ref "MCU") (pin "17") (pinfunction "GND_17") (pintype "passive+no_connect"))
    )
    (net (code "68") (name "unconnected-(MCU-ON{slash}OFF-Pad15)") (class "Default")
      (node (ref "MCU") (pin "15") (pinfunction "ON/OFF_15") (pintype "passive+no_connect"))
    )
    (net (code "69") (name "unconnected-(MCU-PROGRAM-Pad16)") (class "Default")
      (node (ref "MCU") (pin "16") (pinfunction "PROGRAM_16") (pintype "passive+no_connect"))
    )
    (net (code "70") (name "unconnected-(MCU-VBAT-Pad19)") (class "Default")
      (node (ref "MCU") (pin "19") (pinfunction "VBAT_19") (pintype "passive+no_connect"))
    )
  )
)
